# schema_puissance_fusible.net
KiCad netlist of a schematic drawn in EAGLE
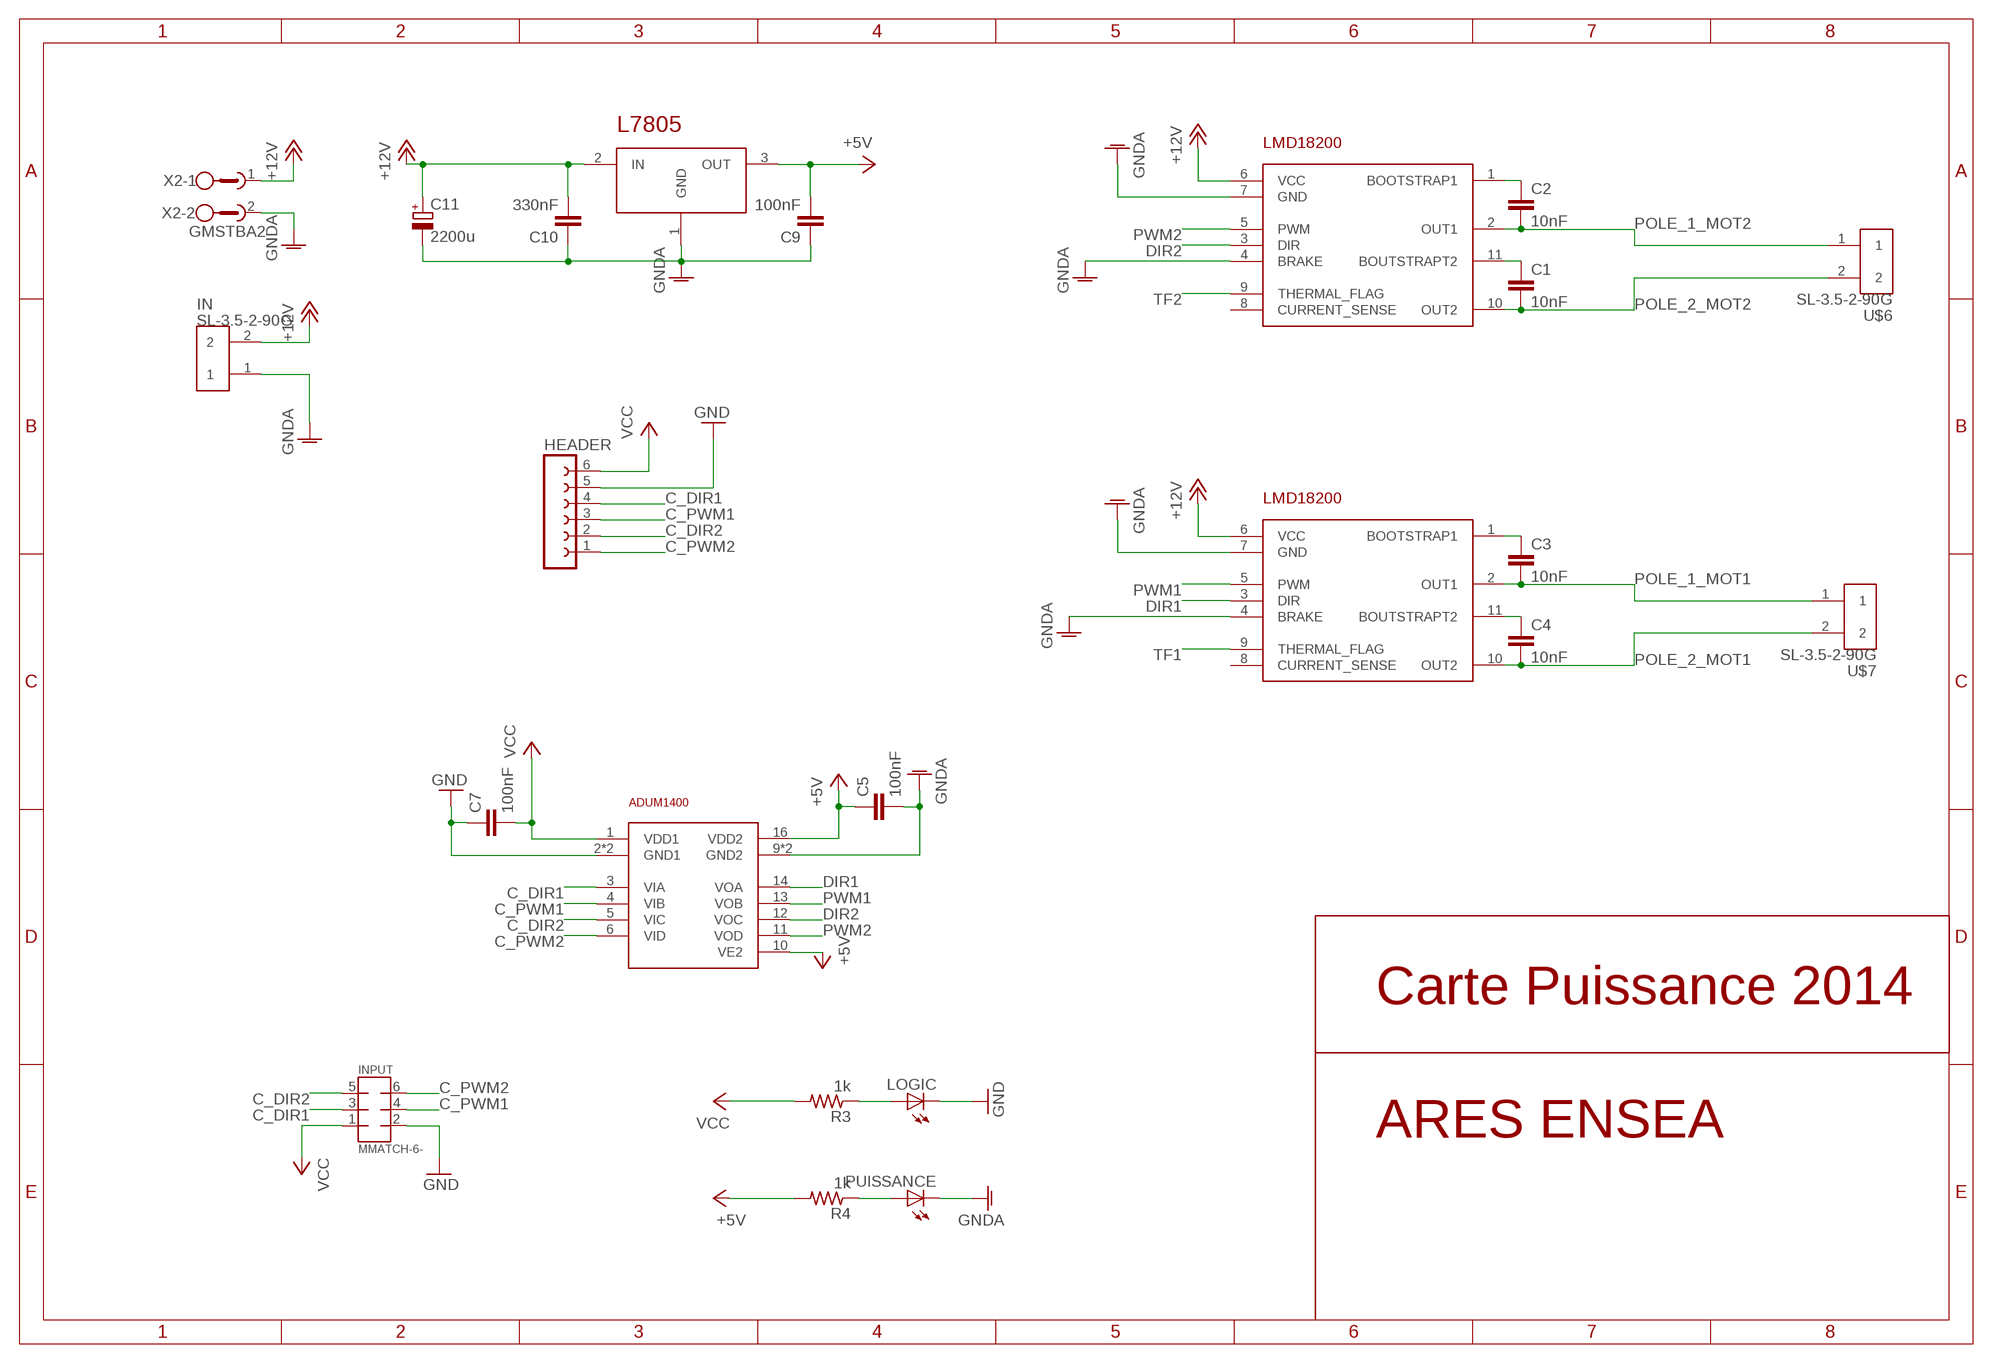
[diagram p0: schematic, sheet 1]

(export (version "E")
  (design (tool "Eeschema 10.0.6"))
  (components
    (comp (ref "C1")
      (value "10nF")
      (footprint "eagle-import:C0805")
      (libsource (lib "eagle-import") (part "C-EUC0805"))
    )
    (comp (ref "C2")
      (value "10nF")
      (footprint "eagle-import:C0805")
      (libsource (lib "eagle-import") (part "C-EUC0805"))
    )
    (comp (ref "C3")
      (value "10nF")
      (footprint "eagle-import:C0805")
      (libsource (lib "eagle-import") (part "C-EUC0805"))
    )
    (comp (ref "C4")
      (value "10nF")
      (footprint "eagle-import:C0805")
      (libsource (lib "eagle-import") (part "C-EUC0805"))
    )
    (comp (ref "C5")
      (value "100nF")
      (footprint "eagle-import:C0805")
      (libsource (lib "eagle-import") (part "C-EUC0805"))
    )
    (comp (ref "C7")
      (value "100nF")
      (footprint "eagle-import:C0805")
      (libsource (lib "eagle-import") (part "C-EUC0805"))
    )
    (comp (ref "C9")
      (value "100nF")
      (footprint "eagle-import:C0805")
      (libsource (lib "eagle-import") (part "C-EUC0805"))
    )
    (comp (ref "C10")
      (value "330nF")
      (footprint "eagle-import:C0805")
      (libsource (lib "eagle-import") (part "C-EUC0805"))
    )
    (comp (ref "C11")
      (value "2200u")
      (footprint "eagle-import:TT5D11")
      (libsource (lib "eagle-import") (part "CPOL-EUTT5D11"))
    )
    (comp (ref "HEADER")
      (value "FE06-1")
      (footprint "eagle-import:FE06")
      (libsource (lib "eagle-import") (part "FE06-1"))
    )
    (comp (ref "IN")
      (value "SL-3.5-2-90G")
      (footprint "eagle-import:SL-3.5-2-90G")
      (libsource (lib "eagle-import") (part "SL-3.5-2-90G"))
    )
    (comp (ref "INPUT")
      (value "MMATCH-6-")
      (footprint "eagle-import:AMP-215079-6")
      (libsource (lib "eagle-import") (part "MMATCH-6-"))
    )
    (comp (ref "LOGIC")
      (value "LEDSML0805")
      (footprint "eagle-import:SML0805")
      (libsource (lib "eagle-import") (part "LEDSML0805"))
    )
    (comp (ref "PUISSANCE")
      (value "LEDSML0805")
      (footprint "eagle-import:SML0805")
      (libsource (lib "eagle-import") (part "LEDSML0805"))
    )
    (comp (ref "R3")
      (value "1k")
      (footprint "eagle-import:M0805")
      (libsource (lib "eagle-import") (part "R-US_M0805"))
    )
    (comp (ref "R4")
      (value "1k")
      (footprint "eagle-import:M0805")
      (libsource (lib "eagle-import") (part "R-US_M0805"))
    )
    (comp (ref "U$1")
      (value "LMD18200")
      (footprint "eagle-import:LMD18200")
      (libsource (lib "eagle-import") (part "LMD18200"))
    )
    (comp (ref "U$2")
      (value "LMD18200")
      (footprint "eagle-import:LMD18200")
      (libsource (lib "eagle-import") (part "LMD18200"))
    )
    (comp (ref "U$3")
      (value "ADUM1400S")
      (footprint "eagle-import:SO-16W")
      (libsource (lib "eagle-import") (part "ADUM1400S"))
    )
    (comp (ref "U$5")
      (value "L7805TO263")
      (footprint "eagle-import:DPAK")
      (libsource (lib "eagle-import") (part "L7805TO263"))
    )
    (comp (ref "U$6")
      (value "SL-3.5-2-90G")
      (footprint "eagle-import:SL-3.5-2-90G")
      (libsource (lib "eagle-import") (part "SL-3.5-2-90G"))
    )
    (comp (ref "U$7")
      (value "SL-3.5-2-90G")
      (footprint "eagle-import:SL-3.5-2-90G")
      (libsource (lib "eagle-import") (part "SL-3.5-2-90G"))
    )
    (comp (ref "X2")
      (value "GMSTBA2")
      (footprint "eagle-import:GMSTBA2")
      (fields (field (name "MF") "FARNELL") (field (name "MPN") "1757242"))
      (libsource (lib "eagle-import") (part "GMSTBA2"))
    )
  )
  (nets
    (net (code "1") (name "+5V") (class "Default")
      (node (ref "C5") (pin "1") (pinfunction "1_1") (pintype "passive"))
      (node (ref "C9") (pin "2") (pinfunction "2_2") (pintype "passive"))
      (node (ref "R4") (pin "2") (pinfunction "2_2") (pintype "passive"))
      (node (ref "U$3") (pin "10") (pinfunction "VE2_10") (pintype "bidirectional"))
      (node (ref "U$3") (pin "16") (pinfunction "VDD2_16") (pintype "bidirectional"))
      (node (ref "U$5") (pin "3") (pinfunction "OUT_3") (pintype "bidirectional"))
    )
    (net (code "2") (name "+12V") (class "Default")
      (node (ref "C10") (pin "2") (pinfunction "2_2") (pintype "passive"))
      (node (ref "C11") (pin "+") (pinfunction "+_+") (pintype "passive"))
      (node (ref "IN") (pin "2") (pinfunction "2_2") (pintype "bidirectional"))
      (node (ref "U$1") (pin "6") (pinfunction "VCC_6") (pintype "bidirectional"))
      (node (ref "U$2") (pin "6") (pinfunction "VCC_6") (pintype "bidirectional"))
      (node (ref "U$5") (pin "2") (pinfunction "IN_2") (pintype "bidirectional"))
      (node (ref "X2") (pin "1") (pinfunction "1_1") (pintype "passive"))
    )
    (net (code "3") (name "/C_DIR1") (class "Default")
      (node (ref "HEADER") (pin "4") (pinfunction "4_4") (pintype "passive"))
      (node (ref "INPUT") (pin "3") (pinfunction "5_3") (pintype "bidirectional"))
      (node (ref "U$3") (pin "3") (pinfunction "VIA_3") (pintype "bidirectional"))
    )
    (net (code "4") (name "/C_DIR2") (class "Default")
      (node (ref "HEADER") (pin "2") (pinfunction "2_2") (pintype "passive"))
      (node (ref "INPUT") (pin "5") (pinfunction "7_5") (pintype "bidirectional"))
      (node (ref "U$3") (pin "5") (pinfunction "VIC_5") (pintype "bidirectional"))
    )
    (net (code "5") (name "/C_PWM1") (class "Default")
      (node (ref "HEADER") (pin "3") (pinfunction "3_3") (pintype "passive"))
      (node (ref "INPUT") (pin "4") (pinfunction "6_4") (pintype "bidirectional"))
      (node (ref "U$3") (pin "4") (pinfunction "VIB_4") (pintype "bidirectional"))
    )
    (net (code "6") (name "/C_PWM2") (class "Default")
      (node (ref "HEADER") (pin "1") (pinfunction "1_1") (pintype "passive"))
      (node (ref "INPUT") (pin "6") (pinfunction "8_6") (pintype "bidirectional"))
      (node (ref "U$3") (pin "6") (pinfunction "VID_6") (pintype "bidirectional"))
    )
    (net (code "7") (name "/DIR1") (class "Default")
      (node (ref "U$1") (pin "3") (pinfunction "DIR_3") (pintype "bidirectional"))
      (node (ref "U$3") (pin "14") (pinfunction "VOA_14") (pintype "bidirectional"))
    )
    (net (code "8") (name "/DIR2") (class "Default")
      (node (ref "U$2") (pin "3") (pinfunction "DIR_3") (pintype "bidirectional"))
      (node (ref "U$3") (pin "12") (pinfunction "VOC_12") (pintype "bidirectional"))
    )
    (net (code "9") (name "/POLE_1_MOT1") (class "Default")
      (node (ref "C3") (pin "2") (pinfunction "2_2") (pintype "passive"))
      (node (ref "U$1") (pin "2") (pinfunction "OUT1_2") (pintype "bidirectional"))
      (node (ref "U$7") (pin "1") (pinfunction "1_1") (pintype "bidirectional"))
    )
    (net (code "10") (name "/POLE_1_MOT2") (class "Default")
      (node (ref "C2") (pin "2") (pinfunction "2_2") (pintype "passive"))
      (node (ref "U$2") (pin "2") (pinfunction "OUT1_2") (pintype "bidirectional"))
      (node (ref "U$6") (pin "1") (pinfunction "1_1") (pintype "bidirectional"))
    )
    (net (code "11") (name "/POLE_2_MOT1") (class "Default")
      (node (ref "C4") (pin "2") (pinfunction "2_2") (pintype "passive"))
      (node (ref "U$1") (pin "10") (pinfunction "OUT2_10") (pintype "bidirectional"))
      (node (ref "U$7") (pin "2") (pinfunction "2_2") (pintype "bidirectional"))
    )
    (net (code "12") (name "/POLE_2_MOT2") (class "Default")
      (node (ref "C1") (pin "2") (pinfunction "2_2") (pintype "passive"))
      (node (ref "U$2") (pin "10") (pinfunction "OUT2_10") (pintype "bidirectional"))
      (node (ref "U$6") (pin "2") (pinfunction "2_2") (pintype "bidirectional"))
    )
    (net (code "13") (name "/PWM1") (class "Default")
      (node (ref "U$1") (pin "5") (pinfunction "PWM_5") (pintype "bidirectional"))
      (node (ref "U$3") (pin "13") (pinfunction "VOB_13") (pintype "bidirectional"))
    )
    (net (code "14") (name "/PWM2") (class "Default")
      (node (ref "U$2") (pin "5") (pinfunction "PWM_5") (pintype "bidirectional"))
      (node (ref "U$3") (pin "11") (pinfunction "VOD_11") (pintype "bidirectional"))
    )
    (net (code "15") (name "/TF1") (class "Default")
      (node (ref "U$1") (pin "9") (pinfunction "THERMAL_FLAG_9") (pintype "bidirectional"))
    )
    (net (code "16") (name "/TF2") (class "Default")
      (node (ref "U$2") (pin "9") (pinfunction "THERMAL_FLAG_9") (pintype "bidirectional"))
    )
    (net (code "17") (name "GND") (class "Default")
      (node (ref "C7") (pin "1") (pinfunction "1_1") (pintype "passive"))
      (node (ref "HEADER") (pin "5") (pinfunction "5_5") (pintype "passive"))
      (node (ref "INPUT") (pin "2") (pinfunction "4_2") (pintype "bidirectional"))
      (node (ref "LOGIC") (pin "C") (pinfunction "C_C") (pintype "passive"))
      (node (ref "U$3") (pin "2") (pinfunction "GND1_2") (pintype "bidirectional"))
      (node (ref "U$3") (pin "8") (pinfunction "GND1_8") (pintype "bidirectional"))
    )
    (net (code "18") (name "GNDA") (class "Default")
      (node (ref "C10") (pin "1") (pinfunction "1_1") (pintype "passive"))
      (node (ref "C11") (pin "-") (pinfunction "-_-") (pintype "passive"))
      (node (ref "C5") (pin "2") (pinfunction "2_2") (pintype "passive"))
      (node (ref "C9") (pin "1") (pinfunction "1_1") (pintype "passive"))
      (node (ref "IN") (pin "1") (pinfunction "1_1") (pintype "bidirectional"))
      (node (ref "PUISSANCE") (pin "C") (pinfunction "C_C") (pintype "passive"))
      (node (ref "U$1") (pin "4") (pinfunction "BRAKE_4") (pintype "bidirectional"))
      (node (ref "U$1") (pin "7") (pinfunction "GND_7") (pintype "bidirectional"))
      (node (ref "U$2") (pin "4") (pinfunction "BRAKE_4") (pintype "bidirectional"))
      (node (ref "U$2") (pin "7") (pinfunction "GND_7") (pintype "bidirectional"))
      (node (ref "U$3") (pin "15") (pinfunction "GND2_15") (pintype "bidirectional"))
      (node (ref "U$3") (pin "9") (pinfunction "GND2_9") (pintype "bidirectional"))
      (node (ref "U$5") (pin "1") (pinfunction "GND_1") (pintype "bidirectional"))
      (node (ref "X2") (pin "2") (pinfunction "1_2") (pintype "passive"))
    )
    (net (code "19") (name "Net-(LOGIC-PadA)") (class "Default")
      (node (ref "LOGIC") (pin "A") (pinfunction "A_A") (pintype "passive"))
      (node (ref "R3") (pin "1") (pinfunction "1_1") (pintype "passive"))
    )
    (net (code "20") (name "Net-(PUISSANCE-PadA)") (class "Default")
      (node (ref "PUISSANCE") (pin "A") (pinfunction "A_A") (pintype "passive"))
      (node (ref "R4") (pin "1") (pinfunction "1_1") (pintype "passive"))
    )
    (net (code "21") (name "Net-(U$1-BOOTSTRAP1)") (class "Default")
      (node (ref "C3") (pin "1") (pinfunction "1_1") (pintype "passive"))
      (node (ref "U$1") (pin "1") (pinfunction "BOOTSTRAP1_1") (pintype "bidirectional"))
    )
    (net (code "22") (name "Net-(U$1-BOUTSTRAPT2)") (class "Default")
      (node (ref "C4") (pin "1") (pinfunction "1_1") (pintype "passive"))
      (node (ref "U$1") (pin "11") (pinfunction "BOUTSTRAPT2_11") (pintype "bidirectional"))
    )
    (net (code "23") (name "Net-(U$2-BOOTSTRAP1)") (class "Default")
      (node (ref "C2") (pin "1") (pinfunction "1_1") (pintype "passive"))
      (node (ref "U$2") (pin "1") (pinfunction "BOOTSTRAP1_1") (pintype "bidirectional"))
    )
    (net (code "24") (name "Net-(U$2-BOUTSTRAPT2)") (class "Default")
      (node (ref "C1") (pin "1") (pinfunction "1_1") (pintype "passive"))
      (node (ref "U$2") (pin "11") (pinfunction "BOUTSTRAPT2_11") (pintype "bidirectional"))
    )
    (net (code "25") (name "VCC") (class "Default")
      (node (ref "C7") (pin "2") (pinfunction "2_2") (pintype "passive"))
      (node (ref "HEADER") (pin "6") (pinfunction "6_6") (pintype "passive"))
      (node (ref "INPUT") (pin "1") (pinfunction "3_1") (pintype "bidirectional"))
      (node (ref "R3") (pin "2") (pinfunction "2_2") (pintype "passive"))
      (node (ref "U$3") (pin "1") (pinfunction "VDD1_1") (pintype "bidirectional"))
    )
    (net (code "26") (name "unconnected-(U$1-CURRENT_SENSE-Pad8)") (class "Default")
      (node (ref "U$1") (pin "8") (pinfunction "CURRENT_SENSE_8") (pintype "bidirectional"))
    )
    (net (code "27") (name "unconnected-(U$2-CURRENT_SENSE-Pad8)") (class "Default")
      (node (ref "U$2") (pin "8") (pinfunction "CURRENT_SENSE_8") (pintype "bidirectional"))
    )
  )
)
